# MotorController.net
KiCad netlist of a schematic drawn in EAGLE
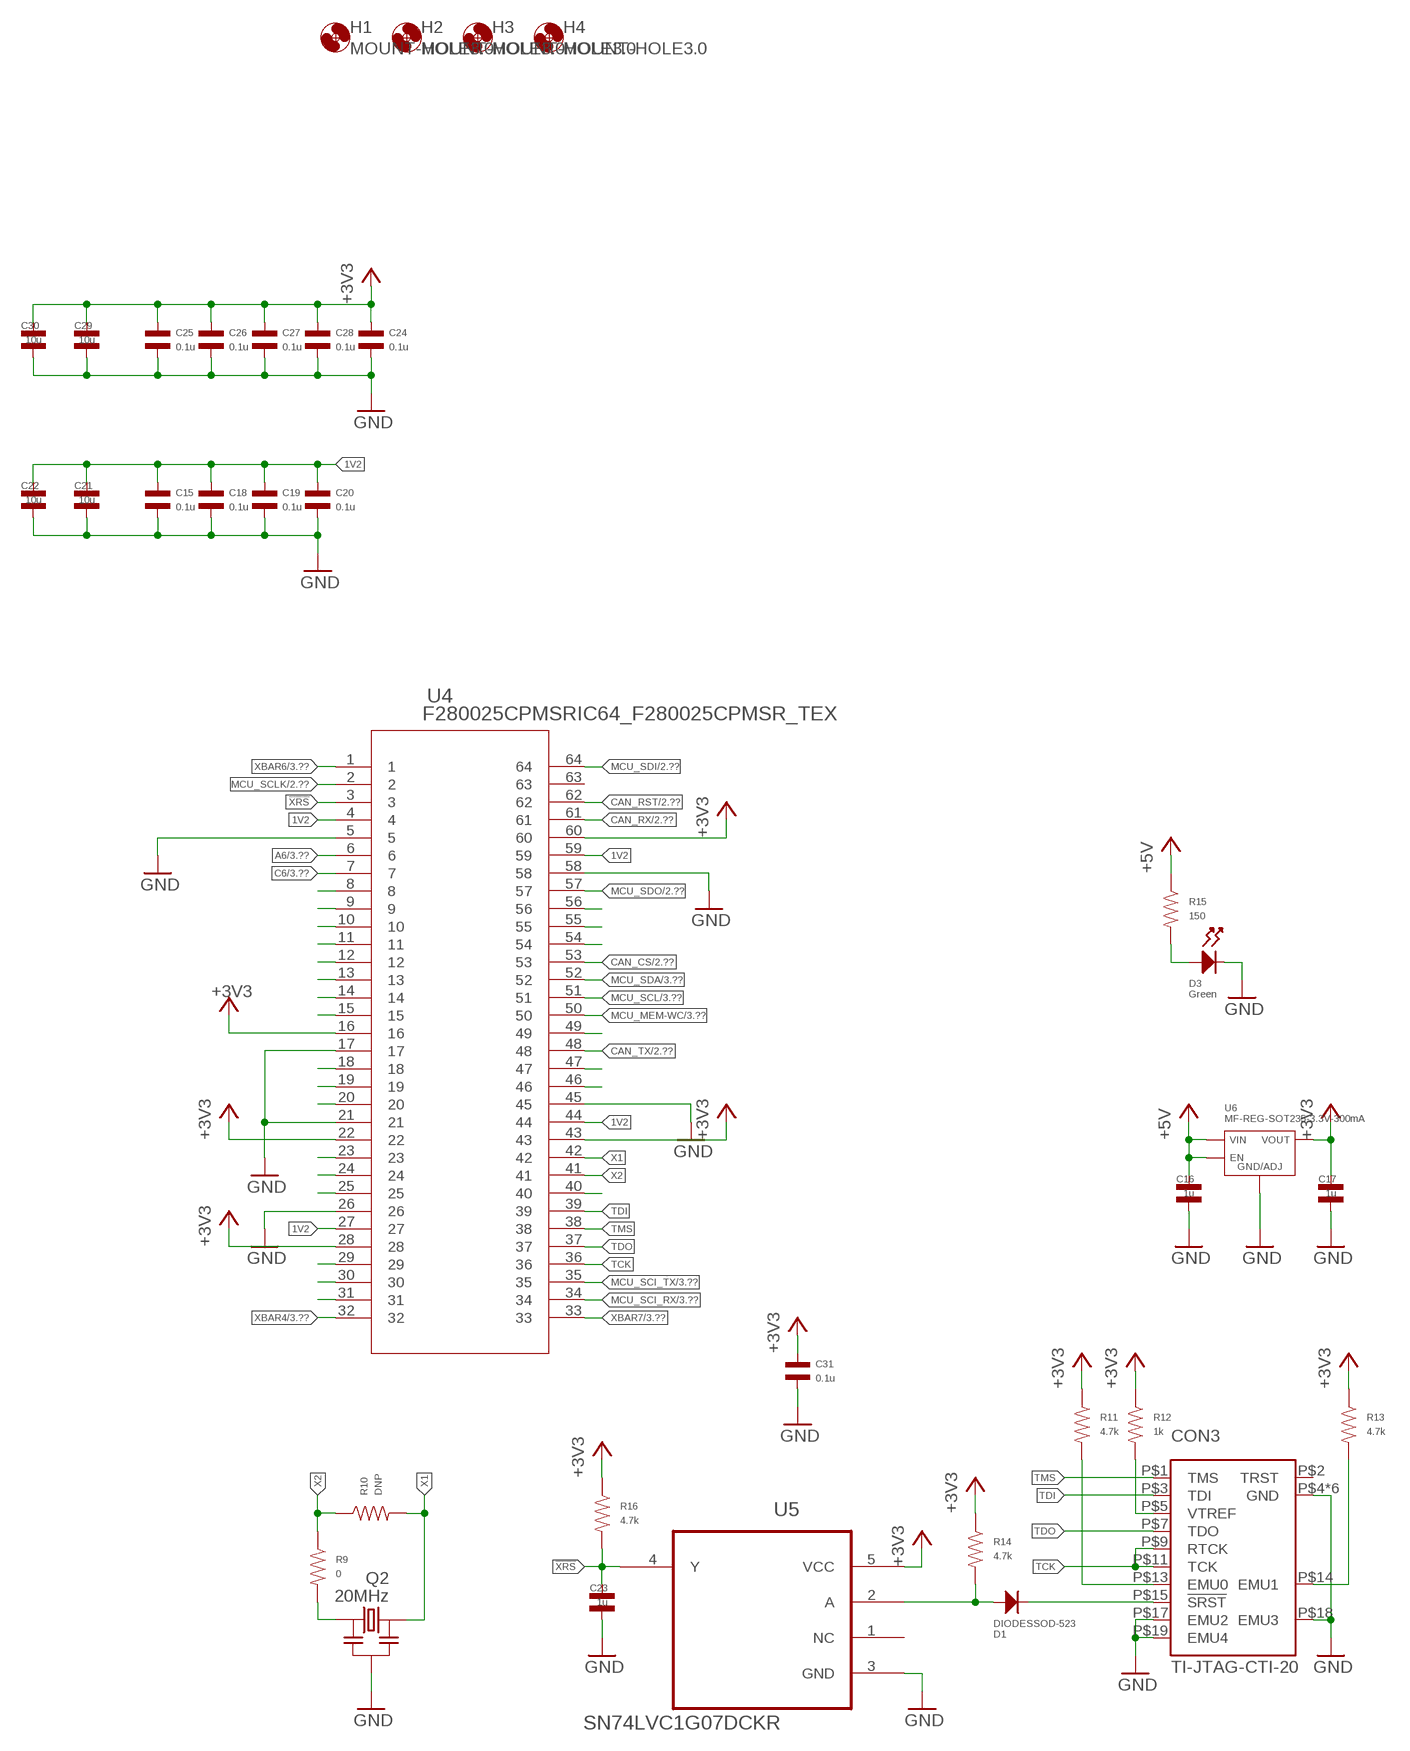
[diagram p0: schematic, sheet 1]
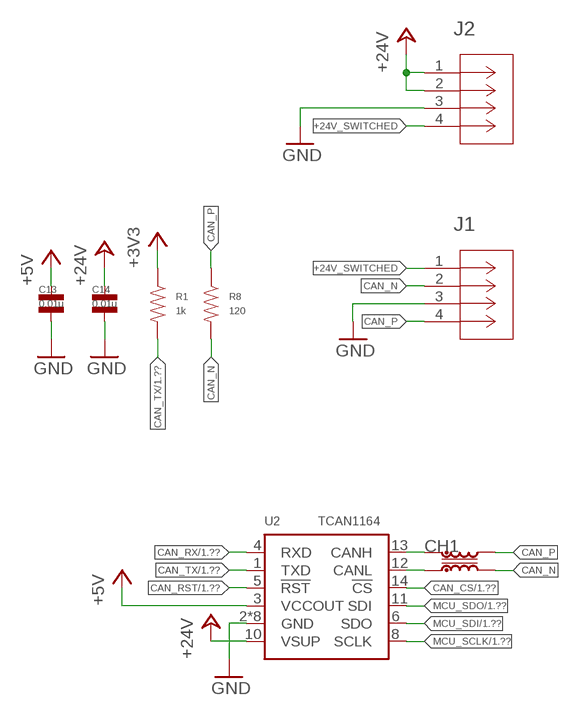
[diagram p1: schematic, sheet 2]
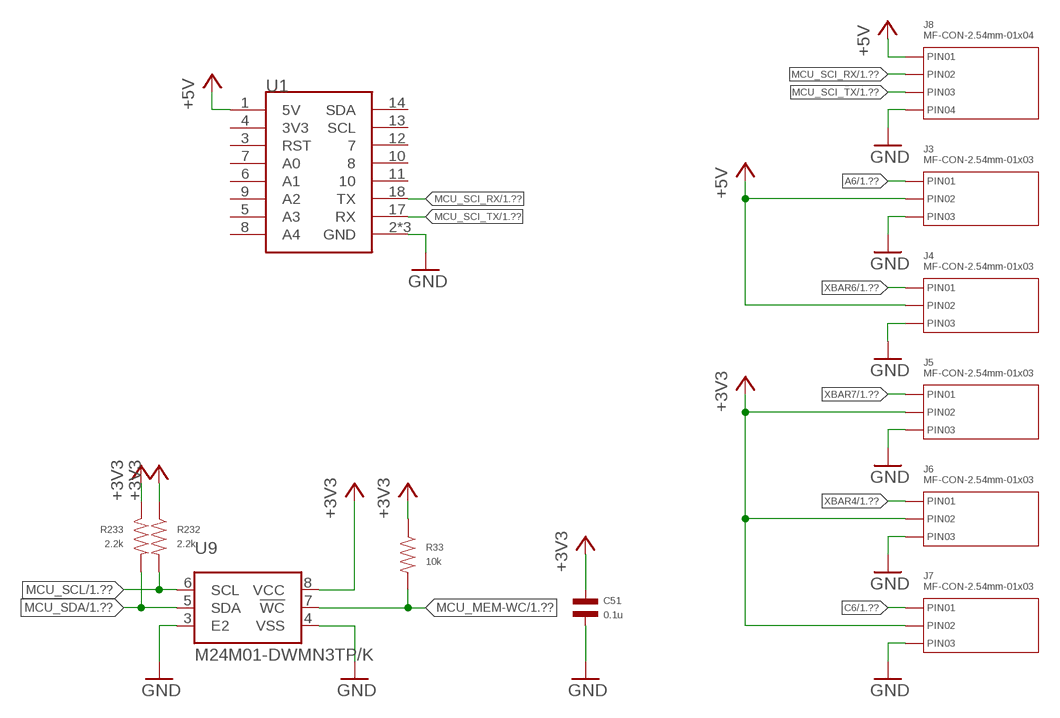
[diagram p2: schematic, sheet 3]

(export (version "E")
  (design (tool "Eeschema 10.0.6"))
  (components
    (comp (ref "C13")
      (value "0.01u")
      (footprint "eagle-import:C0402")
      (fields (field (name "MPN") "CL05B103KB5NNNC"))
      (libsource (lib "eagle-import") (part "CAPACITOR_NP_0402"))
    )
    (comp (ref "C14")
      (value "0.01u")
      (footprint "eagle-import:C0402")
      (fields (field (name "MPN") "CL05B103KB5NNNC"))
      (libsource (lib "eagle-import") (part "CAPACITOR_NP_0402"))
    )
    (comp (ref "CH1")
      (value "CHOKE-COMMON_MODECM1210-LAIRD")
      (footprint "eagle-import:CM1210-LAIRD")
      (fields (field (name "MPN") "CM1210B104R-1A"))
      (libsource (lib "eagle-import") (part "CHOKE-COMMON_MODECM1210-LAIRD"))
    )
    (comp (ref "J1")
      (value "768250004CON_768250004_MOL")
      (footprint "eagle-import:CON_768250004_MOL")
      (fields
        (field (name "MANUFACTURER_PART_NUMBER") "768250004")
        (field (name "MPN") "0768250004")
        (field (name "COPYRIGHT") "Copyright (C) 2024 Ultra Librarian. All rights reserved.")
      )
      (libsource (lib "eagle-import") (part "768250004CON_768250004_MOL"))
    )
    (comp (ref "J2")
      (value "768250004CON_768250004_MOL")
      (footprint "eagle-import:CON_768250004_MOL")
      (fields
        (field (name "MANUFACTURER_PART_NUMBER") "768250004")
        (field (name "MPN") "0768250004")
        (field (name "COPYRIGHT") "Copyright (C) 2024 Ultra Librarian. All rights reserved.")
      )
      (libsource (lib "eagle-import") (part "768250004CON_768250004_MOL"))
    )
    (comp (ref "R1")
      (value "1k")
      (footprint "eagle-import:R0402")
      (fields (field (name "MPN") "ERJ-2RKF1001X"))
      (libsource (lib "eagle-import") (part "RESISTOR_0402"))
    )
    (comp (ref "R8")
      (value "120")
      (footprint "eagle-import:R0402")
      (fields (field (name "MPN") "ERJ-2GEJ121X"))
      (libsource (lib "eagle-import") (part "RESISTOR_0402"))
    )
    (comp (ref "U2")
      (value "TCAN1164")
      (footprint "eagle-import:CONV_TPS63021DSJ")
      (fields (field (name "MPN") "TCAN1164DMTRQ1"))
      (libsource (lib "eagle-import") (part "TCAN1164"))
    )
    (comp (ref "C51")
      (value "0.1u")
      (footprint "eagle-import:C0402")
      (fields (field (name "MPN") "GCM155R71H104KE02D"))
      (libsource (lib "eagle-import") (part "MF_Passives_4704077_CAPACITOR_NP_0402"))
    )
    (comp (ref "J3")
      (value "MF-CON-2.54mm-01x03")
      (footprint "eagle-import:PTH_2.54MM_01X03")
      (fields (field (name "HOUSEPART") "YES"))
      (libsource (lib "eagle-import") (part "CON_01X03_PTH_2.54MM"))
    )
    (comp (ref "J4")
      (value "MF-CON-2.54mm-01x03")
      (footprint "eagle-import:PTH_2.54MM_01X03")
      (fields (field (name "HOUSEPART") "YES"))
      (libsource (lib "eagle-import") (part "CON_01X03_PTH_2.54MM"))
    )
    (comp (ref "J5")
      (value "MF-CON-2.54mm-01x03")
      (footprint "eagle-import:PTH_2.54MM_01X03")
      (fields (field (name "HOUSEPART") "YES"))
      (libsource (lib "eagle-import") (part "CON_01X03_PTH_2.54MM"))
    )
    (comp (ref "J6")
      (value "MF-CON-2.54mm-01x03")
      (footprint "eagle-import:PTH_2.54MM_01X03")
      (fields (field (name "HOUSEPART") "YES"))
      (libsource (lib "eagle-import") (part "CON_01X03_PTH_2.54MM"))
    )
    (comp (ref "J7")
      (value "MF-CON-2.54mm-01x03")
      (footprint "eagle-import:PTH_2.54MM_01X03")
      (fields (field (name "HOUSEPART") "YES"))
      (libsource (lib "eagle-import") (part "CON_01X03_PTH_2.54MM"))
    )
    (comp (ref "J8")
      (value "MF-CON-2.54mm-01x04")
      (footprint "eagle-import:PTH_2.54MM_01X04")
      (fields (field (name "HOUSEPART") "YES"))
      (libsource (lib "eagle-import") (part "CON_01X04_PTH_2.54MM"))
    )
    (comp (ref "R33")
      (value "10k")
      (footprint "eagle-import:R0402")
      (fields (field (name "MPN") "ERJ-2RKF1002X"))
      (libsource (lib "eagle-import") (part "MF_Passives_4704077_RESISTOR_0402"))
    )
    (comp (ref "R232")
      (value "2.2k")
      (footprint "eagle-import:R0402")
      (fields (field (name "MPN") "ERJ-2RKF2201X"))
      (libsource (lib "eagle-import") (part "MF_Passives_4704077_RESISTOR_0402"))
    )
    (comp (ref "R233")
      (value "2.2k")
      (footprint "eagle-import:R0402")
      (fields (field (name "MPN") "ERJ-2RKF2201X"))
      (libsource (lib "eagle-import") (part "MF_Passives_4704077_RESISTOR_0402"))
    )
    (comp (ref "U1")
      (value "ESP32-C3")
      (footprint "eagle-import:ESP32-C3")
      (libsource (lib "eagle-import") (part "ESP32-C3"))
    )
    (comp (ref "U9")
      (value "M24M01-DWMN3TP/K")
      (footprint "eagle-import:SOIC-8")
      (libsource (lib "eagle-import") (part "M24M02-DWMN3TP/K"))
    )
    (comp (ref "C15")
      (value "0.1u")
      (footprint "eagle-import:C0402")
      (fields (field (name "MPN") "GCM155R71H104KE02D"))
      (libsource (lib "eagle-import") (part "CAPACITOR_NP_0402"))
    )
    (comp (ref "C16")
      (value "1u")
      (footprint "eagle-import:C0805")
      (fields (field (name "MPN") "CL21B105KAFNNNE"))
      (libsource (lib "eagle-import") (part "CAPACITOR_NP_0805"))
    )
    (comp (ref "C17")
      (value "1u")
      (footprint "eagle-import:C0805")
      (fields (field (name "MPN") "CL21B105KAFNNNE"))
      (libsource (lib "eagle-import") (part "CAPACITOR_NP_0805"))
    )
    (comp (ref "C18")
      (value "0.1u")
      (footprint "eagle-import:C0402")
      (fields (field (name "MPN") "GCM155R71H104KE02D"))
      (libsource (lib "eagle-import") (part "CAPACITOR_NP_0402"))
    )
    (comp (ref "C19")
      (value "0.1u")
      (footprint "eagle-import:C0402")
      (fields (field (name "MPN") "GCM155R71H104KE02D"))
      (libsource (lib "eagle-import") (part "CAPACITOR_NP_0402"))
    )
    (comp (ref "C20")
      (value "0.1u")
      (footprint "eagle-import:C0402")
      (fields (field (name "MPN") "GCM155R71H104KE02D"))
      (libsource (lib "eagle-import") (part "CAPACITOR_NP_0402"))
    )
    (comp (ref "C21")
      (value "10u")
      (footprint "eagle-import:C0805")
      (fields (field (name "MPN") "CL21A106KAYNNNE"))
      (libsource (lib "eagle-import") (part "CAPACITOR_NP_0805"))
    )
    (comp (ref "C22")
      (value "10u")
      (footprint "eagle-import:C0805")
      (fields (field (name "MPN") "CL21A106KAYNNNE"))
      (libsource (lib "eagle-import") (part "CAPACITOR_NP_0805"))
    )
    (comp (ref "C23")
      (value "1u")
      (footprint "eagle-import:C0402")
      (fields (field (name "MPN") "CL05A105KA5NQNC"))
      (libsource (lib "eagle-import") (part "CAPACITOR_NP_0402"))
    )
    (comp (ref "C24")
      (value "0.1u")
      (footprint "eagle-import:C0402")
      (fields (field (name "MPN") "GCM155R71H104KE02D"))
      (libsource (lib "eagle-import") (part "CAPACITOR_NP_0402"))
    )
    (comp (ref "C25")
      (value "0.1u")
      (footprint "eagle-import:C0402")
      (fields (field (name "MPN") "GCM155R71H104KE02D"))
      (libsource (lib "eagle-import") (part "CAPACITOR_NP_0402"))
    )
    (comp (ref "C26")
      (value "0.1u")
      (footprint "eagle-import:C0402")
      (fields (field (name "MPN") "GCM155R71H104KE02D"))
      (libsource (lib "eagle-import") (part "CAPACITOR_NP_0402"))
    )
    (comp (ref "C27")
      (value "0.1u")
      (footprint "eagle-import:C0402")
      (fields (field (name "MPN") "GCM155R71H104KE02D"))
      (libsource (lib "eagle-import") (part "CAPACITOR_NP_0402"))
    )
    (comp (ref "C28")
      (value "0.1u")
      (footprint "eagle-import:C0402")
      (fields (field (name "MPN") "GCM155R71H104KE02D"))
      (libsource (lib "eagle-import") (part "CAPACITOR_NP_0402"))
    )
    (comp (ref "C29")
      (value "10u")
      (footprint "eagle-import:C0805")
      (fields (field (name "MPN") "CL21A106KAYNNNE"))
      (libsource (lib "eagle-import") (part "CAPACITOR_NP_0805"))
    )
    (comp (ref "C30")
      (value "10u")
      (footprint "eagle-import:C0805")
      (fields (field (name "MPN") "CL21A106KAYNNNE"))
      (libsource (lib "eagle-import") (part "CAPACITOR_NP_0805"))
    )
    (comp (ref "C31")
      (value "0.1u")
      (footprint "eagle-import:C0402")
      (fields (field (name "MPN") "GCM155R71H104KE02D"))
      (libsource (lib "eagle-import") (part "MF_Passives_4704077_CAPACITOR_NP_0402"))
    )
    (comp (ref "CON3")
      (value "TI-JTAG-CTI-20")
      (footprint "eagle-import:FTR-110-51-L-D-06")
      (fields (field (name "MPN") "FTR-110-51-L-D-06"))
      (libsource (lib "eagle-import") (part "TI-JTAG-CTI-20"))
    )
    (comp (ref "D1")
      (value "DIODESSOD-523")
      (footprint "eagle-import:SOD523")
      (fields (field (name "MPN") "RB510SM-40FHT2R"))
      (libsource (lib "eagle-import") (part "DIODESSOD-523"))
    )
    (comp (ref "D3")
      (value "Green")
      (footprint "eagle-import:LED0603")
      (fields (field (name "HOUSEPART") "NO") (field (name "MPN") "SML-E12P8WT86"))
      (libsource (lib "eagle-import") (part "LED_SINGLE-0603"))
    )
    (comp (ref "H1")
      (value "MOUNT-HOLE3.0")
      (footprint "eagle-import:3,0")
      (libsource (lib "eagle-import") (part "MOUNT-HOLE3.0"))
    )
    (comp (ref "H2")
      (value "MOUNT-HOLE3.0")
      (footprint "eagle-import:3,0")
      (libsource (lib "eagle-import") (part "MOUNT-HOLE3.0"))
    )
    (comp (ref "H3")
      (value "MOUNT-HOLE3.0")
      (footprint "eagle-import:3,0")
      (libsource (lib "eagle-import") (part "MOUNT-HOLE3.0"))
    )
    (comp (ref "H4")
      (value "MOUNT-HOLE3.0")
      (footprint "eagle-import:3,0")
      (libsource (lib "eagle-import") (part "MOUNT-HOLE3.0"))
    )
    (comp (ref "Q2")
      (value "20MHz")
      (footprint "eagle-import:CSTNE")
      (fields (field (name "MPN") "CSTNE20M0V53C000R0"))
      (libsource (lib "eagle-import") (part "RESONATORCSTNE"))
    )
    (comp (ref "R9")
      (value "0")
      (footprint "eagle-import:R0402")
      (fields (field (name "MPN") "ERJ-2GE0R00X"))
      (libsource (lib "eagle-import") (part "RESISTOR_0402"))
    )
    (comp (ref "R10")
      (value "DNP")
      (footprint "eagle-import:R0402")
      (libsource (lib "eagle-import") (part "RESISTOR_0402"))
    )
    (comp (ref "R11")
      (value "4.7k")
      (footprint "eagle-import:R0402")
      (fields (field (name "MPN") "ERJ-2RKF4701X"))
      (libsource (lib "eagle-import") (part "RESISTOR_0402"))
    )
    (comp (ref "R12")
      (value "1k")
      (footprint "eagle-import:R0402")
      (fields (field (name "MPN") "ERJ-2RKF1001X"))
      (libsource (lib "eagle-import") (part "RESISTOR_0402"))
    )
    (comp (ref "R13")
      (value "4.7k")
      (footprint "eagle-import:R0402")
      (fields (field (name "MPN") "ERJ-2RKF4701X"))
      (libsource (lib "eagle-import") (part "RESISTOR_0402"))
    )
    (comp (ref "R14")
      (value "4.7k")
      (footprint "eagle-import:R0402")
      (fields (field (name "MPN") "ERJ-2RKF4701X"))
      (libsource (lib "eagle-import") (part "RESISTOR_0402"))
    )
    (comp (ref "R15")
      (value "150")
      (footprint "eagle-import:R0805")
      (fields (field (name "MPN") "ERJ-6GEYJ151V"))
      (libsource (lib "eagle-import") (part "RESISTOR_0805"))
    )
    (comp (ref "R16")
      (value "4.7k")
      (footprint "eagle-import:R0402")
      (fields (field (name "MPN") "ERJ-2RKF4701X"))
      (libsource (lib "eagle-import") (part "RESISTOR_0402"))
    )
    (comp (ref "U4")
      (value "F280025CPMSRIC64_F280025CPMSR_TEX")
      (footprint "eagle-import:IC64_F280025CPMSR_TEX")
      (fields
        (field (name "MANUFACTURER_PART_NUMBER") "F280025CPMSR")
        (field (name "COPYRIGHT") "Copyright (C) 2024 Ultra Librarian. All rights reserved.")
      )
      (libsource (lib "eagle-import") (part "F280025CPMSRIC64_F280025CPMSR_TEX"))
    )
    (comp (ref "U5")
      (value "SN74LVC1G07DCKR")
      (footprint "eagle-import:SOT65P210X110-5N")
      (libsource (lib "eagle-import") (part "SN74LVC1G07DCKR"))
    )
    (comp (ref "U6")
      (value "MF-REG-SOT235-3.3V-300mA")
      (footprint "eagle-import:SOT-23-5")
      (fields (field (name "HOUSEPART") "YES") (field (name "MPN") "TLV70233PDBVR"))
      (libsource (lib "eagle-import") (part "TLV70233PDBVR"))
    )
  )
  (nets
    (net (code "1") (name "+3V3") (class "Default")
      (node (ref "C17") (pin "P$1") (pinfunction "P$1_P$1") (pintype "passive"))
      (node (ref "C24") (pin "P$1") (pinfunction "P$1_P$1") (pintype "passive"))
      (node (ref "C25") (pin "P$1") (pinfunction "P$1_P$1") (pintype "passive"))
      (node (ref "C26") (pin "P$1") (pinfunction "P$1_P$1") (pintype "passive"))
      (node (ref "C27") (pin "P$1") (pinfunction "P$1_P$1") (pintype "passive"))
      (node (ref "C28") (pin "P$1") (pinfunction "P$1_P$1") (pintype "passive"))
      (node (ref "C29") (pin "P$1") (pinfunction "P$1_P$1") (pintype "passive"))
      (node (ref "C30") (pin "P$1") (pinfunction "P$1_P$1") (pintype "passive"))
      (node (ref "C31") (pin "P$1") (pinfunction "P$1_P$1") (pintype "passive"))
      (node (ref "C51") (pin "P$1") (pinfunction "P$1_P$1") (pintype "passive"))
      (node (ref "J5") (pin "P$2") (pinfunction "PIN2_P$2") (pintype "bidirectional"))
      (node (ref "J6") (pin "P$2") (pinfunction "PIN2_P$2") (pintype "bidirectional"))
      (node (ref "J7") (pin "P$2") (pinfunction "PIN2_P$2") (pintype "bidirectional"))
      (node (ref "R1") (pin "P$1") (pinfunction "P$1_P$1") (pintype "passive"))
      (node (ref "R11") (pin "P$1") (pinfunction "P$1_P$1") (pintype "passive"))
      (node (ref "R12") (pin "P$1") (pinfunction "P$1_P$1") (pintype "passive"))
      (node (ref "R13") (pin "P$1") (pinfunction "P$1_P$1") (pintype "passive"))
      (node (ref "R14") (pin "P$1") (pinfunction "P$1_P$1") (pintype "passive"))
      (node (ref "R16") (pin "P$1") (pinfunction "P$1_P$1") (pintype "passive"))
      (node (ref "R232") (pin "P$1") (pinfunction "P$1_P$1") (pintype "passive"))
      (node (ref "R233") (pin "P$1") (pinfunction "P$1_P$1") (pintype "passive"))
      (node (ref "R33") (pin "P$1") (pinfunction "P$1_P$1") (pintype "passive"))
      (node (ref "U4") (pin "16") (pinfunction "16_16") (pintype "passive"))
      (node (ref "U4") (pin "22") (pinfunction "22_22") (pintype "passive"))
      (node (ref "U4") (pin "28") (pinfunction "28_28") (pintype "passive"))
      (node (ref "U4") (pin "43") (pinfunction "43_43") (pintype "passive"))
      (node (ref "U4") (pin "60") (pinfunction "60_60") (pintype "passive"))
      (node (ref "U5") (pin "5") (pinfunction "VCC_5") (pintype "power_in"))
      (node (ref "U6") (pin "P$5") (pinfunction "VOUT_P$5") (pintype "bidirectional"))
      (node (ref "U9") (pin "8") (pinfunction "VCC_8") (pintype "power_in"))
    )
    (net (code "2") (name "+5V") (class "Default")
      (node (ref "C13") (pin "P$1") (pinfunction "P$1_P$1") (pintype "passive"))
      (node (ref "C16") (pin "P$1") (pinfunction "P$1_P$1") (pintype "passive"))
      (node (ref "J3") (pin "P$2") (pinfunction "PIN2_P$2") (pintype "bidirectional"))
      (node (ref "J4") (pin "P$2") (pinfunction "PIN2_P$2") (pintype "bidirectional"))
      (node (ref "J8") (pin "P$1") (pinfunction "PIN1_P$1") (pintype "bidirectional"))
      (node (ref "R15") (pin "P$1") (pinfunction "P$1_P$1") (pintype "passive"))
      (node (ref "U1") (pin "1") (pinfunction "5V_1") (pintype "bidirectional"))
      (node (ref "U2") (pin "3") (pinfunction "VCCOUT_3") (pintype "bidirectional"))
      (node (ref "U6") (pin "P$1") (pinfunction "VIN_P$1") (pintype "bidirectional"))
      (node (ref "U6") (pin "P$3") (pinfunction "EN_P$3") (pintype "bidirectional"))
    )
    (net (code "3") (name "+24V") (class "Default")
      (node (ref "C14") (pin "P$1") (pinfunction "P$1_P$1") (pintype "passive"))
      (node (ref "J2") (pin "1") (pinfunction "1_1") (pintype "passive"))
      (node (ref "J2") (pin "2") (pinfunction "2_2") (pintype "passive"))
      (node (ref "U2") (pin "10") (pinfunction "VSUP_10") (pintype "bidirectional"))
    )
    (net (code "4") (name "+24V_SWITCHED") (class "Default")
      (node (ref "J1") (pin "1") (pinfunction "1_1") (pintype "passive"))
      (node (ref "J2") (pin "4") (pinfunction "4_4") (pintype "passive"))
    )
    (net (code "5") (name "1V2") (class "Default")
      (node (ref "C15") (pin "P$1") (pinfunction "P$1_P$1") (pintype "passive"))
      (node (ref "C18") (pin "P$1") (pinfunction "P$1_P$1") (pintype "passive"))
      (node (ref "C19") (pin "P$1") (pinfunction "P$1_P$1") (pintype "passive"))
      (node (ref "C20") (pin "P$1") (pinfunction "P$1_P$1") (pintype "passive"))
      (node (ref "C21") (pin "P$1") (pinfunction "P$1_P$1") (pintype "passive"))
      (node (ref "C22") (pin "P$1") (pinfunction "P$1_P$1") (pintype "passive"))
      (node (ref "U4") (pin "27") (pinfunction "27_27") (pintype "passive"))
      (node (ref "U4") (pin "4") (pinfunction "4_4") (pintype "passive"))
      (node (ref "U4") (pin "44") (pinfunction "44_44") (pintype "passive"))
      (node (ref "U4") (pin "59") (pinfunction "59_59") (pintype "passive"))
    )
    (net (code "6") (name "A6") (class "Default")
      (node (ref "J3") (pin "P$1") (pinfunction "PIN1_P$1") (pintype "bidirectional"))
      (node (ref "U4") (pin "6") (pinfunction "6_6") (pintype "passive"))
    )
    (net (code "7") (name "C6") (class "Default")
      (node (ref "J7") (pin "P$1") (pinfunction "PIN1_P$1") (pintype "bidirectional"))
      (node (ref "U4") (pin "7") (pinfunction "7_7") (pintype "passive"))
    )
    (net (code "8") (name "CAN_CS") (class "Default")
      (node (ref "U2") (pin "14") (pinfunction "~{CS}_14") (pintype "bidirectional"))
      (node (ref "U4") (pin "53") (pinfunction "53_53") (pintype "passive"))
    )
    (net (code "9") (name "CAN_N") (class "Default")
      (node (ref "CH1") (pin "P$3") (pinfunction "3_P$3") (pintype "bidirectional"))
      (node (ref "J1") (pin "2") (pinfunction "2_2") (pintype "passive"))
      (node (ref "R8") (pin "P$2") (pinfunction "P$2_P$2") (pintype "passive"))
    )
    (net (code "10") (name "CAN_P") (class "Default")
      (node (ref "CH1") (pin "P$2") (pinfunction "2_P$2") (pintype "bidirectional"))
      (node (ref "J1") (pin "4") (pinfunction "4_4") (pintype "passive"))
      (node (ref "R8") (pin "P$1") (pinfunction "P$1_P$1") (pintype "passive"))
    )
    (net (code "11") (name "CAN_RST") (class "Default")
      (node (ref "U2") (pin "5") (pinfunction "~{RST}_5") (pintype "bidirectional"))
      (node (ref "U4") (pin "62") (pinfunction "62_62") (pintype "passive"))
    )
    (net (code "12") (name "CAN_RX") (class "Default")
      (node (ref "U2") (pin "4") (pinfunction "RXD_4") (pintype "bidirectional"))
      (node (ref "U4") (pin "61") (pinfunction "61_61") (pintype "passive"))
    )
    (net (code "13") (name "CAN_TX") (class "Default")
      (node (ref "R1") (pin "P$2") (pinfunction "P$2_P$2") (pintype "passive"))
      (node (ref "U2") (pin "1") (pinfunction "TXD_1") (pintype "bidirectional"))
      (node (ref "U4") (pin "48") (pinfunction "48_48") (pintype "passive"))
    )
    (net (code "14") (name "GND") (class "Default")
      (node (ref "C13") (pin "P$2") (pinfunction "P$2_P$2") (pintype "passive"))
      (node (ref "C14") (pin "P$2") (pinfunction "P$2_P$2") (pintype "passive"))
      (node (ref "C15") (pin "P$2") (pinfunction "P$2_P$2") (pintype "passive"))
      (node (ref "C16") (pin "P$2") (pinfunction "P$2_P$2") (pintype "passive"))
      (node (ref "C17") (pin "P$2") (pinfunction "P$2_P$2") (pintype "passive"))
      (node (ref "C18") (pin "P$2") (pinfunction "P$2_P$2") (pintype "passive"))
      (node (ref "C19") (pin "P$2") (pinfunction "P$2_P$2") (pintype "passive"))
      (node (ref "C20") (pin "P$2") (pinfunction "P$2_P$2") (pintype "passive"))
      (node (ref "C21") (pin "P$2") (pinfunction "P$2_P$2") (pintype "passive"))
      (node (ref "C22") (pin "P$2") (pinfunction "P$2_P$2") (pintype "passive"))
      (node (ref "C23") (pin "P$2") (pinfunction "P$2_P$2") (pintype "passive"))
      (node (ref "C24") (pin "P$2") (pinfunction "P$2_P$2") (pintype "passive"))
      (node (ref "C25") (pin "P$2") (pinfunction "P$2_P$2") (pintype "passive"))
      (node (ref "C26") (pin "P$2") (pinfunction "P$2_P$2") (pintype "passive"))
      (node (ref "C27") (pin "P$2") (pinfunction "P$2_P$2") (pintype "passive"))
      (node (ref "C28") (pin "P$2") (pinfunction "P$2_P$2") (pintype "passive"))
      (node (ref "C29") (pin "P$2") (pinfunction "P$2_P$2") (pintype "passive"))
      (node (ref "C30") (pin "P$2") (pinfunction "P$2_P$2") (pintype "passive"))
      (node (ref "C31") (pin "P$2") (pinfunction "P$2_P$2") (pintype "passive"))
      (node (ref "C51") (pin "P$2") (pinfunction "P$2_P$2") (pintype "passive"))
      (node (ref "CON3") (pin "P$10") (pinfunction "GND_P$10") (pintype "bidirectional"))
      (node (ref "CON3") (pin "P$12") (pinfunction "GND_P$12") (pintype "bidirectional"))
      (node (ref "CON3") (pin "P$16") (pinfunction "GND_P$16") (pintype "bidirectional"))
      (node (ref "CON3") (pin "P$17") (pinfunction "EMU2_P$17") (pintype "bidirectional"))
      (node (ref "CON3") (pin "P$18") (pinfunction "EMU3_P$18") (pintype "bidirectional"))
      (node (ref "CON3") (pin "P$19") (pinfunction "EMU4_P$19") (pintype "bidirectional"))
      (node (ref "CON3") (pin "P$20") (pinfunction "GND_P$20") (pintype "bidirectional"))
      (node (ref "CON3") (pin "P$4") (pinfunction "GND_P$4") (pintype "bidirectional"))
      (node (ref "CON3") (pin "P$8") (pinfunction "GND_P$8") (pintype "bidirectional"))
      (node (ref "D3") (pin "CATHODE") (pinfunction "CATHODE_CATHODE") (pintype "power_in"))
      (node (ref "J1") (pin "3") (pinfunction "3_3") (pintype "passive"))
      (node (ref "J2") (pin "3") (pinfunction "3_3") (pintype "passive"))
      (node (ref "J3") (pin "P$3") (pinfunction "PIN3_P$3") (pintype "bidirectional"))
      (node (ref "J4") (pin "P$3") (pinfunction "PIN3_P$3") (pintype "bidirectional"))
      (node (ref "J5") (pin "P$3") (pinfunction "PIN3_P$3") (pintype "bidirectional"))
      (node (ref "J6") (pin "P$3") (pinfunction "PIN3_P$3") (pintype "bidirectional"))
      (node (ref "J7") (pin "P$3") (pinfunction "PIN3_P$3") (pintype "bidirectional"))
      (node (ref "J8") (pin "P$4") (pinfunction "PIN4_P$4") (pintype "bidirectional"))
      (node (ref "Q2") (pin "2") (pinfunction "GND_2") (pintype "passive"))
      (node (ref "U1") (pin "15") (pinfunction "GND_15") (pintype "bidirectional"))
      (node (ref "U1") (pin "16") (pinfunction "GND_16") (pintype "bidirectional"))
      (node (ref "U1") (pin "2") (pinfunction "GND_2") (pintype "bidirectional"))
      (node (ref "U2") (pin "15") (pinfunction "GND_15") (pintype "bidirectional"))
      (node (ref "U2") (pin "15_1") (pinfunction "GND_15_1") (pintype "bidirectional"))
      (node (ref "U2") (pin "15_2") (pinfunction "GND_15_2") (pintype "bidirectional"))
      (node (ref "U2") (pin "15_3") (pinfunction "GND_15_3") (pintype "bidirectional"))
      (node (ref "U2") (pin "15_4") (pinfunction "GND_15_4") (pintype "bidirectional"))
      (node (ref "U2") (pin "15_5") (pinfunction "GND_15_5") (pintype "bidirectional"))
      (node (ref "U2") (pin "15_6") (pinfunction "GND_15_6") (pintype "bidirectional"))
      (node (ref "U2") (pin "2") (pinfunction "GND_2") (pintype "bidirectional"))
      (node (ref "U4") (pin "17") (pinfunction "17_17") (pintype "passive"))
      (node (ref "U4") (pin "21") (pinfunction "21_21") (pintype "passive"))
      (node (ref "U4") (pin "26") (pinfunction "26_26") (pintype "passive"))
      (node (ref "U4") (pin "45") (pinfunction "45_45") (pintype "passive"))
      (node (ref "U4") (pin "5") (pinfunction "5_5") (pintype "passive"))
      (node (ref "U4") (pin "58") (pinfunction "58_58") (pintype "passive"))
      (node (ref "U5") (pin "3") (pinfunction "GND_3") (pintype "passive"))
      (node (ref "U6") (pin "P$2") (pinfunction "GND/ADJ_P$2") (pintype "bidirectional"))
      (node (ref "U9") (pin "3") (pinfunction "E2_3") (pintype "power_in"))
      (node (ref "U9") (pin "4") (pinfunction "VSS_4") (pintype "power_in"))
    )
    (net (code "15") (name "MCU_MEM-WC") (class "Default")
      (node (ref "R33") (pin "P$2") (pinfunction "P$2_P$2") (pintype "passive"))
      (node (ref "U4") (pin "50") (pinfunction "50_50") (pintype "passive"))
      (node (ref "U9") (pin "7") (pinfunction "~{WC}_7") (pintype "power_in"))
    )
    (net (code "16") (name "MCU_SCI_RX") (class "Default")
      (node (ref "J8") (pin "P$2") (pinfunction "PIN2_P$2") (pintype "bidirectional"))
      (node (ref "U1") (pin "18") (pinfunction "TX_18") (pintype "bidirectional"))
      (node (ref "U4") (pin "34") (pinfunction "34_34") (pintype "passive"))
    )
    (net (code "17") (name "MCU_SCI_TX") (class "Default")
      (node (ref "J8") (pin "P$3") (pinfunction "PIN3_P$3") (pintype "bidirectional"))
      (node (ref "U1") (pin "17") (pinfunction "RX_17") (pintype "bidirectional"))
      (node (ref "U4") (pin "35") (pinfunction "35_35") (pintype "passive"))
    )
    (net (code "18") (name "MCU_SCL") (class "Default")
      (node (ref "R232") (pin "P$2") (pinfunction "P$2_P$2") (pintype "passive"))
      (node (ref "U4") (pin "51") (pinfunction "51_51") (pintype "passive"))
      (node (ref "U9") (pin "6") (pinfunction "SCL_6") (pintype "power_in"))
    )
    (net (code "19") (name "MCU_SCLK") (class "Default")
      (node (ref "U2") (pin "8") (pinfunction "SCLK_8") (pintype "bidirectional"))
      (node (ref "U4") (pin "2") (pinfunction "2_2") (pintype "passive"))
    )
    (net (code "20") (name "MCU_SDA") (class "Default")
      (node (ref "R233") (pin "P$2") (pinfunction "P$2_P$2") (pintype "passive"))
      (node (ref "U4") (pin "52") (pinfunction "52_52") (pintype "passive"))
      (node (ref "U9") (pin "5") (pinfunction "SDA_5") (pintype "power_in"))
    )
    (net (code "21") (name "MCU_SDI") (class "Default")
      (node (ref "U2") (pin "6") (pinfunction "SDO_6") (pintype "bidirectional"))
      (node (ref "U4") (pin "64") (pinfunction "64_64") (pintype "passive"))
    )
    (net (code "22") (name "MCU_SDO") (class "Default")
      (node (ref "U2") (pin "11") (pinfunction "SDI_11") (pintype "bidirectional"))
      (node (ref "U4") (pin "57") (pinfunction "57_57") (pintype "passive"))
    )
    (net (code "23") (name "Net-(CH1-1)") (class "Default")
      (node (ref "CH1") (pin "P$1") (pinfunction "1_P$1") (pintype "bidirectional"))
      (node (ref "U2") (pin "13") (pinfunction "CANH_13") (pintype "bidirectional"))
    )
    (net (code "24") (name "Net-(CH1-4)") (class "Default")
      (node (ref "CH1") (pin "P$4") (pinfunction "4_P$4") (pintype "bidirectional"))
      (node (ref "U2") (pin "12") (pinfunction "CANL_12") (pintype "bidirectional"))
    )
    (net (code "25") (name "Net-(CON3-EMU0)") (class "Default")
      (node (ref "CON3") (pin "P$13") (pinfunction "EMU0_P$13") (pintype "bidirectional"))
      (node (ref "R11") (pin "P$2") (pinfunction "P$2_P$2") (pintype "passive"))
    )
    (net (code "26") (name "Net-(CON3-EMU1)") (class "Default")
      (node (ref "CON3") (pin "P$14") (pinfunction "EMU1_P$14") (pintype "bidirectional"))
      (node (ref "R13") (pin "P$2") (pinfunction "P$2_P$2") (pintype "passive"))
    )
    (net (code "27") (name "Net-(CON3-VTREF)") (class "Default")
      (node (ref "CON3") (pin "P$5") (pinfunction "VTREF_P$5") (pintype "bidirectional"))
      (node (ref "R12") (pin "P$2") (pinfunction "P$2_P$2") (pintype "passive"))
    )
    (net (code "28") (name "Net-(CON3-~{SRST})") (class "Default")
      (node (ref "CON3") (pin "P$15") (pinfunction "~{SRST}_P$15") (pintype "bidirectional"))
      (node (ref "D1") (pin "C") (pinfunction "CATHODE_C") (pintype "bidirectional"))
    )
    (net (code "29") (name "Net-(D1-ANODE)") (class "Default")
      (node (ref "D1") (pin "A") (pinfunction "ANODE_A") (pintype "bidirectional"))
      (node (ref "R14") (pin "P$2") (pinfunction "P$2_P$2") (pintype "passive"))
      (node (ref "U5") (pin "2") (pinfunction "A_2") (pintype "input"))
    )
    (net (code "30") (name "Net-(D3-PadANODE)") (class "Default")
      (node (ref "D3") (pin "ANODE") (pinfunction "ANODE_ANODE") (pintype "power_in"))
      (node (ref "R15") (pin "P$2") (pinfunction "P$2_P$2") (pintype "passive"))
    )
    (net (code "31") (name "Net-(Q2-XOUT)") (class "Default")
      (node (ref "Q2") (pin "3") (pinfunction "XOUT_3") (pintype "passive"))
      (node (ref "R9") (pin "P$2") (pinfunction "P$2_P$2") (pintype "passive"))
    )
    (net (code "32") (name "TCK") (class "Default")
      (node (ref "CON3") (pin "P$11") (pinfunction "TCK_P$11") (pintype "bidirectional"))
      (node (ref "CON3") (pin "P$9") (pinfunction "RTCK_P$9") (pintype "bidirectional"))
      (node (ref "U4") (pin "36") (pinfunction "36_36") (pintype "passive"))
    )
    (net (code "33") (name "TDI") (class "Default")
      (node (ref "CON3") (pin "P$3") (pinfunction "TDI_P$3") (pintype "bidirectional"))
      (node (ref "U4") (pin "39") (pinfunction "39_39") (pintype "passive"))
    )
    (net (code "34") (name "TDO") (class "Default")
      (node (ref "CON3") (pin "P$7") (pinfunction "TDO_P$7") (pintype "bidirectional"))
      (node (ref "U4") (pin "37") (pinfunction "37_37") (pintype "passive"))
    )
    (net (code "35") (name "TMS") (class "Default")
      (node (ref "CON3") (pin "P$1") (pinfunction "TMS_P$1") (pintype "bidirectional"))
      (node (ref "U4") (pin "38") (pinfunction "38_38") (pintype "passive"))
    )
    (net (code "36") (name "X1") (class "Default")
      (node (ref "Q2") (pin "1") (pinfunction "XIN_1") (pintype "passive"))
      (node (ref "R10") (pin "P$2") (pinfunction "P$2_P$2") (pintype "passive"))
      (node (ref "U4") (pin "42") (pinfunction "42_42") (pintype "passive"))
    )
    (net (code "37") (name "X2") (class "Default")
      (node (ref "R10") (pin "P$1") (pinfunction "P$1_P$1") (pintype "passive"))
      (node (ref "R9") (pin "P$1") (pinfunction "P$1_P$1") (pintype "passive"))
      (node (ref "U4") (pin "41") (pinfunction "41_41") (pintype "passive"))
    )
    (net (code "38") (name "XBAR4") (class "Default")
      (node (ref "J6") (pin "P$1") (pinfunction "PIN1_P$1") (pintype "bidirectional"))
      (node (ref "U4") (pin "32") (pinfunction "32_32") (pintype "passive"))
    )
    (net (code "39") (name "XBAR6") (class "Default")
      (node (ref "J4") (pin "P$1") (pinfunction "PIN1_P$1") (pintype "bidirectional"))
      (node (ref "U4") (pin "1") (pinfunction "1_1") (pintype "passive"))
    )
    (net (code "40") (name "XBAR7") (class "Default")
      (node (ref "J5") (pin "P$1") (pinfunction "PIN1_P$1") (pintype "bidirectional"))
      (node (ref "U4") (pin "33") (pinfunction "33_33") (pintype "passive"))
    )
    (net (code "41") (name "unconnected-(CON3-TRST-PadP$2)") (class "Default")
      (node (ref "CON3") (pin "P$2") (pinfunction "TRST_P$2") (pintype "bidirectional"))
    )
    (net (code "42") (name "unconnected-(U1-3V3-Pad4)") (class "Default")
      (node (ref "U1") (pin "4") (pinfunction "3V3_4") (pintype "bidirectional"))
    )
    (net (code "43") (name "unconnected-(U1-7-Pad12)") (class "Default")
      (node (ref "U1") (pin "12") (pinfunction "7_12") (pintype "bidirectional"))
    )
    (net (code "44") (name "unconnected-(U1-8-Pad10)") (class "Default")
      (node (ref "U1") (pin "10") (pinfunction "8_10") (pintype "bidirectional"))
    )
    (net (code "45") (name "unconnected-(U1-10-Pad11)") (class "Default")
      (node (ref "U1") (pin "11") (pinfunction "10_11") (pintype "bidirectional"))
    )
    (net (code "46") (name "unconnected-(U1-A0-Pad7)") (class "Default")
      (node (ref "U1") (pin "7") (pinfunction "A0_7") (pintype "bidirectional"))
    )
    (net (code "47") (name "unconnected-(U1-A1-Pad6)") (class "Default")
      (node (ref "U1") (pin "6") (pinfunction "A1_6") (pintype "bidirectional"))
    )
    (net (code "48") (name "unconnected-(U1-A2-Pad9)") (class "Default")
      (node (ref "U1") (pin "9") (pinfunction "A2_9") (pintype "bidirectional"))
    )
    (net (code "49") (name "unconnected-(U1-A3-Pad5)") (class "Default")
      (node (ref "U1") (pin "5") (pinfunction "A3_5") (pintype "bidirectional"))
    )
    (net (code "50") (name "unconnected-(U1-A4-Pad8)") (class "Default")
      (node (ref "U1") (pin "8") (pinfunction "A4_8") (pintype "bidirectional"))
    )
    (net (code "51") (name "unconnected-(U1-RST-Pad3)") (class "Default")
      (node (ref "U1") (pin "3") (pinfunction "RST_3") (pintype "bidirectional"))
    )
    (net (code "52") (name "unconnected-(U1-SCL-Pad13)") (class "Default")
      (node (ref "U1") (pin "13") (pinfunction "SCL_13") (pintype "bidirectional"))
    )
    (net (code "53") (name "unconnected-(U1-SDA-Pad14)") (class "Default")
      (node (ref "U1") (pin "14") (pinfunction "SDA_14") (pintype "bidirectional"))
    )
    (net (code "54") (name "unconnected-(U4-Pad8)") (class "Default")
      (node (ref "U4") (pin "8") (pinfunction "8_8") (pintype "passive"))
    )
    (net (code "55") (name "unconnected-(U4-Pad9)") (class "Default")
      (node (ref "U4") (pin "9") (pinfunction "9_9") (pintype "passive"))
    )
    (net (code "56") (name "unconnected-(U4-Pad10)") (class "Default")
      (node (ref "U4") (pin "10") (pinfunction "10_10") (pintype "passive"))
    )
    (net (code "57") (name "unconnected-(U4-Pad11)") (class "Default")
      (node (ref "U4") (pin "11") (pinfunction "11_11") (pintype "passive"))
    )
    (net (code "58") (name "unconnected-(U4-Pad12)") (class "Default")
      (node (ref "U4") (pin "12") (pinfunction "12_12") (pintype "passive"))
    )
    (net (code "59") (name "unconnected-(U4-Pad13)") (class "Default")
      (node (ref "U4") (pin "13") (pinfunction "13_13") (pintype "passive"))
    )
    (net (code "60") (name "unconnected-(U4-Pad14)") (class "Default")
      (node (ref "U4") (pin "14") (pinfunction "14_14") (pintype "passive"))
    )
    (net (code "61") (name "unconnected-(U4-Pad15)") (class "Default")
      (node (ref "U4") (pin "15") (pinfunction "15_15") (pintype "passive"))
    )
    (net (code "62") (name "unconnected-(U4-Pad18)") (class "Default")
      (node (ref "U4") (pin "18") (pinfunction "18_18") (pintype "passive"))
    )
    (net (code "63") (name "unconnected-(U4-Pad19)") (class "Default")
      (node (ref "U4") (pin "19") (pinfunction "19_19") (pintype "passive"))
    )
    (net (code "64") (name "unconnected-(U4-Pad20)") (class "Default")
      (node (ref "U4") (pin "20") (pinfunction "20_20") (pintype "passive"))
    )
    (net (code "65") (name "unconnected-(U4-Pad23)") (class "Default")
      (node (ref "U4") (pin "23") (pinfunction "23_23") (pintype "passive"))
    )
    (net (code "66") (name "unconnected-(U4-Pad24)") (class "Default")
      (node (ref "U4") (pin "24") (pinfunction "24_24") (pintype "passive"))
    )
    (net (code "67") (name "unconnected-(U4-Pad25)") (class "Default")
      (node (ref "U4") (pin "25") (pinfunction "25_25") (pintype "passive"))
    )
    (net (code "68") (name "unconnected-(U4-Pad29)") (class "Default")
      (node (ref "U4") (pin "29") (pinfunction "29_29") (pintype "passive"))
    )
    (net (code "69") (name "unconnected-(U4-Pad30)") (class "Default")
      (node (ref "U4") (pin "30") (pinfunction "30_30") (pintype "passive"))
    )
    (net (code "70") (name "unconnected-(U4-Pad31)") (class "Default")
      (node (ref "U4") (pin "31") (pinfunction "31_31") (pintype "passive"))
    )
    (net (code "71") (name "unconnected-(U4-Pad40)") (class "Default")
      (node (ref "U4") (pin "40") (pinfunction "40_40") (pintype "passive"))
    )
    (net (code "72") (name "unconnected-(U4-Pad46)") (class "Default")
      (node (ref "U4") (pin "46") (pinfunction "46_46") (pintype "passive"))
    )
    (net (code "73") (name "unconnected-(U4-Pad47)") (class "Default")
      (node (ref "U4") (pin "47") (pinfunction "47_47") (pintype "passive"))
    )
    (net (code "74") (name "unconnected-(U4-Pad49)") (class "Default")
      (node (ref "U4") (pin "49") (pinfunction "49_49") (pintype "passive"))
    )
    (net (code "75") (name "unconnected-(U4-Pad54)") (class "Default")
      (node (ref "U4") (pin "54") (pinfunction "54_54") (pintype "passive"))
    )
    (net (code "76") (name "unconnected-(U4-Pad55)") (class "Default")
      (node (ref "U4") (pin "55") (pinfunction "55_55") (pintype "passive"))
    )
    (net (code "77") (name "unconnected-(U4-Pad56)") (class "Default")
      (node (ref "U4") (pin "56") (pinfunction "56_56") (pintype "passive"))
    )
    (net (code "78") (name "unconnected-(U4-Pad63)") (class "Default")
      (node (ref "U4") (pin "63") (pinfunction "63_63") (pintype "passive"))
    )
    (net (code "79") (name "unconnected-(U5-NC-Pad1)") (class "Default")
      (node (ref "U5") (pin "1") (pinfunction "NC_1") (pintype "no_connect"))
    )
    (net (code "80") (name "~{XRS}") (class "Default")
      (node (ref "C23") (pin "P$1") (pinfunction "P$1_P$1") (pintype "passive"))
      (node (ref "R16") (pin "P$2") (pinfunction "P$2_P$2") (pintype "passive"))
      (node (ref "U4") (pin "3") (pinfunction "3_3") (pintype "passive"))
      (node (ref "U5") (pin "4") (pinfunction "Y_4") (pintype "output"))
    )
  )
)
